# tinyG2Hat.net
KiCad netlist of a schematic drawn in EAGLE
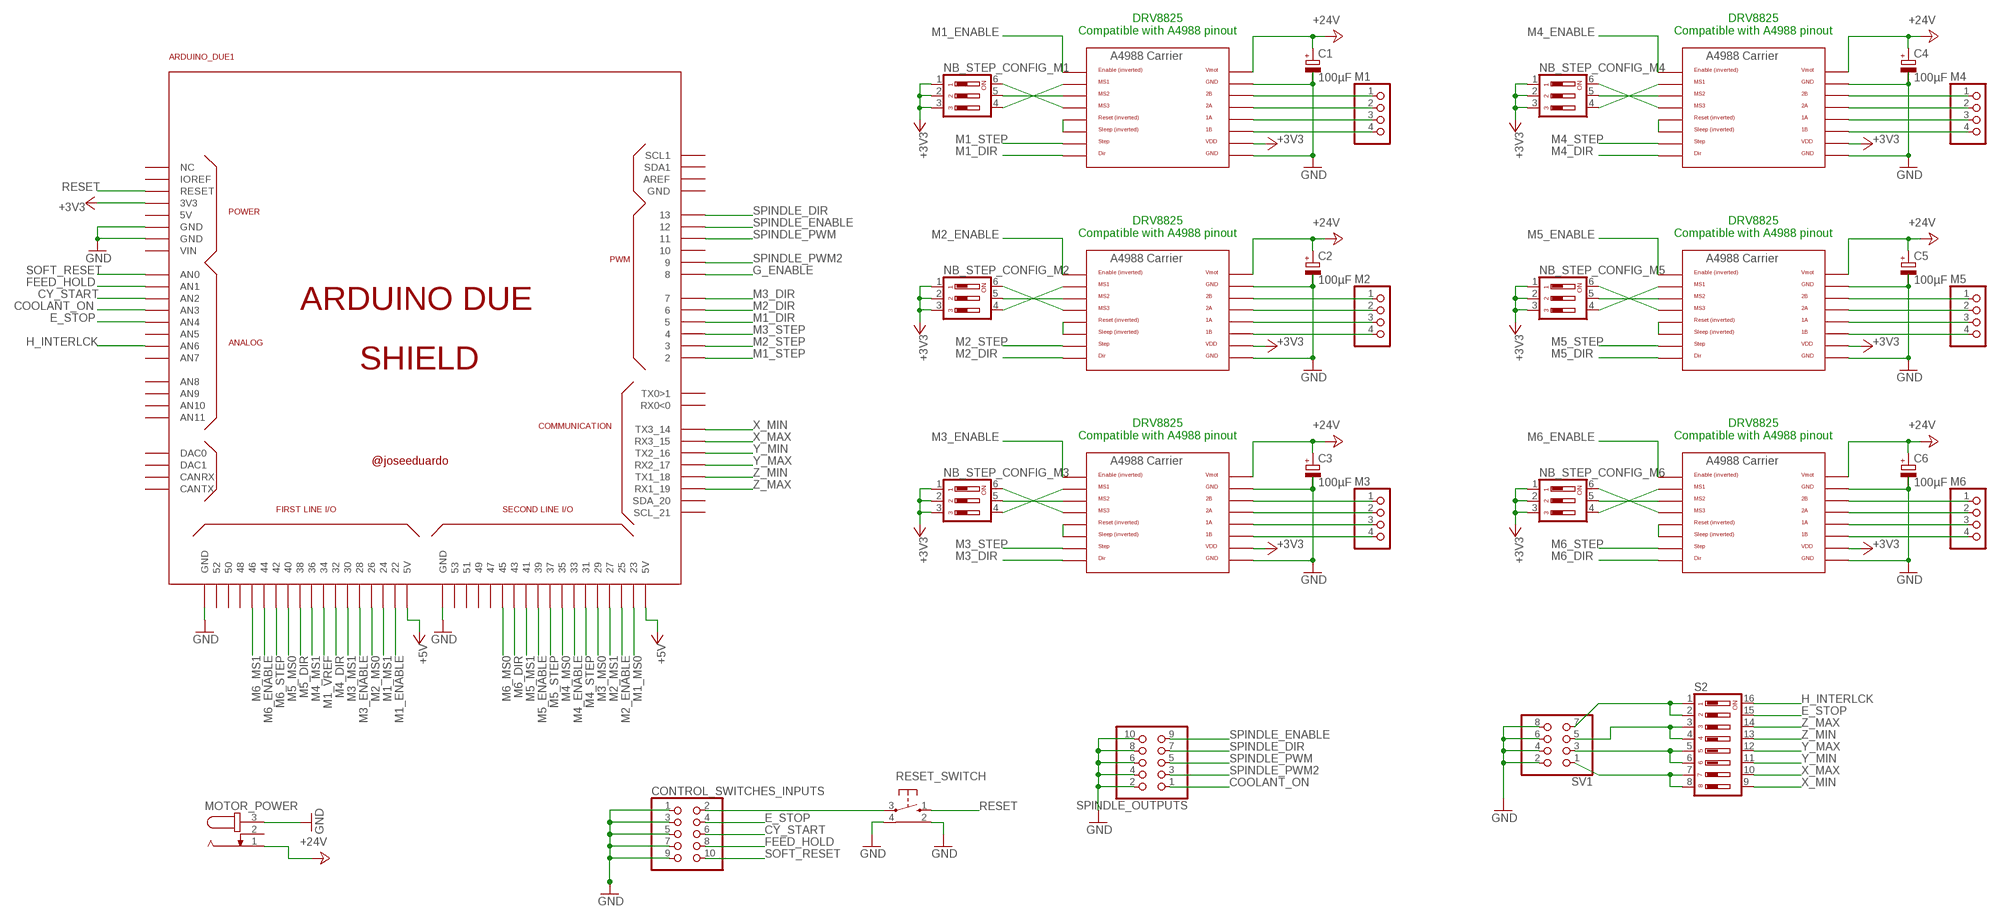
[diagram p0: schematic, sheet 1]

(export (version "E")
  (design (tool "Eeschema 10.0.6"))
  (components
    (comp (ref "ARDUINO_DUE1")
      (value "ARDUINO_DUE_SHIELD_NOSPI")
      (footprint "eagle-import:ARDUINO_DUE_SHIELD_NOSPI")
      (libsource (lib "eagle-import") (part "ARDUINO_DUE_SHIELD_NOSPI"))
    )
    (comp (ref "C1")
      (value "100µF")
      (footprint "eagle-import:E3,5-8")
      (libsource (lib "eagle-import") (part "CPOL-EUE3.5-8"))
    )
    (comp (ref "C2")
      (value "100µF")
      (footprint "eagle-import:E3,5-8")
      (libsource (lib "eagle-import") (part "CPOL-EUE3.5-8"))
    )
    (comp (ref "C3")
      (value "100µF")
      (footprint "eagle-import:E3,5-8")
      (libsource (lib "eagle-import") (part "CPOL-EUE3.5-8"))
    )
    (comp (ref "C4")
      (value "100µF")
      (footprint "eagle-import:E3,5-8")
      (libsource (lib "eagle-import") (part "CPOL-EUE3.5-8"))
    )
    (comp (ref "C5")
      (value "100µF")
      (footprint "eagle-import:E3,5-8")
      (libsource (lib "eagle-import") (part "CPOL-EUE3.5-8"))
    )
    (comp (ref "C6")
      (value "100µF")
      (footprint "eagle-import:E3,5-8")
      (libsource (lib "eagle-import") (part "CPOL-EUE3.5-8"))
    )
    (comp (ref "CONTROL_SWITCHES_INPUTS")
      (value "PINHD-2X5")
      (footprint "eagle-import:2X05")
      (libsource (lib "eagle-import") (part "PINHD-2X5"))
    )
    (comp (ref "M1")
      (value "PINHD-1X4")
      (footprint "eagle-import:1X04")
      (libsource (lib "eagle-import") (part "PINHD-1X4"))
    )
    (comp (ref "M2")
      (value "PINHD-1X4")
      (footprint "eagle-import:1X04")
      (libsource (lib "eagle-import") (part "PINHD-1X4"))
    )
    (comp (ref "M3")
      (value "PINHD-1X4")
      (footprint "eagle-import:1X04")
      (libsource (lib "eagle-import") (part "PINHD-1X4"))
    )
    (comp (ref "M4")
      (value "PINHD-1X4")
      (footprint "eagle-import:1X04")
      (libsource (lib "eagle-import") (part "PINHD-1X4"))
    )
    (comp (ref "M5")
      (value "PINHD-1X4")
      (footprint "eagle-import:1X04")
      (libsource (lib "eagle-import") (part "PINHD-1X4"))
    )
    (comp (ref "M6")
      (value "PINHD-1X4")
      (footprint "eagle-import:1X04")
      (libsource (lib "eagle-import") (part "PINHD-1X4"))
    )
    (comp (ref "MOTOR_POWER")
      (value "RAPC7120")
      (footprint "eagle-import:RAPC712")
      (libsource (lib "eagle-import") (part "RAPC7120"))
    )
    (comp (ref "NB_STEP_CONFIG_M1")
      (value "DIP03YL")
      (footprint "eagle-import:DIP03YL")
      (libsource (lib "eagle-import") (part "DIP03YL"))
    )
    (comp (ref "NB_STEP_CONFIG_M2")
      (value "DIP03YL")
      (footprint "eagle-import:DIP03YL")
      (libsource (lib "eagle-import") (part "DIP03YL"))
    )
    (comp (ref "NB_STEP_CONFIG_M3")
      (value "DIP03YL")
      (footprint "eagle-import:DIP03YL")
      (libsource (lib "eagle-import") (part "DIP03YL"))
    )
    (comp (ref "NB_STEP_CONFIG_M4")
      (value "DIP03YL")
      (footprint "eagle-import:DIP03YL")
      (libsource (lib "eagle-import") (part "DIP03YL"))
    )
    (comp (ref "NB_STEP_CONFIG_M5")
      (value "DIP03YL")
      (footprint "eagle-import:DIP03YL")
      (libsource (lib "eagle-import") (part "DIP03YL"))
    )
    (comp (ref "NB_STEP_CONFIG_M6")
      (value "DIP03YL")
      (footprint "eagle-import:DIP03YL")
      (libsource (lib "eagle-import") (part "DIP03YL"))
    )
    (comp (ref "RESET_SWITCH")
      (value "10-XX-RPAD")
      (footprint "eagle-import:B3F-10XX-RPAD")
      (libsource (lib "eagle-import") (part "10-XX-RPAD"))
    )
    (comp (ref "S2")
      (value "DIP08YL")
      (footprint "eagle-import:DIP08YL")
      (libsource (lib "eagle-import") (part "DIP08YL"))
    )
    (comp (ref "SPINDLE_OUTPUTS")
      (value "PINHD-2X5")
      (footprint "eagle-import:2X05")
      (libsource (lib "eagle-import") (part "PINHD-2X5"))
    )
    (comp (ref "SV1")
      (value "PINHD-2X4")
      (footprint "eagle-import:2X04")
      (libsource (lib "eagle-import") (part "PINHD-2X4"))
    )
    (comp (ref "U$1")
      (value "A4988BREAKOUT")
      (footprint "eagle-import:A4988BREAKOUT")
      (libsource (lib "eagle-import") (part "A4988BREAKOUT"))
    )
    (comp (ref "U$2")
      (value "A4988BREAKOUT")
      (footprint "eagle-import:A4988BREAKOUT")
      (libsource (lib "eagle-import") (part "A4988BREAKOUT"))
    )
    (comp (ref "U$3")
      (value "A4988BREAKOUT")
      (footprint "eagle-import:A4988BREAKOUT")
      (libsource (lib "eagle-import") (part "A4988BREAKOUT"))
    )
    (comp (ref "U$4")
      (value "A4988BREAKOUT")
      (footprint "eagle-import:A4988BREAKOUT")
      (libsource (lib "eagle-import") (part "A4988BREAKOUT"))
    )
    (comp (ref "U$5")
      (value "A4988BREAKOUT")
      (footprint "eagle-import:A4988BREAKOUT")
      (libsource (lib "eagle-import") (part "A4988BREAKOUT"))
    )
    (comp (ref "U$6")
      (value "A4988BREAKOUT")
      (footprint "eagle-import:A4988BREAKOUT")
      (libsource (lib "eagle-import") (part "A4988BREAKOUT"))
    )
  )
  (nets
    (net (code "1") (name "+3V3") (class "Default")
      (node (ref "ARDUINO_DUE1") (pin "3V3") (pinfunction "3V3_3V3") (pintype "bidirectional"))
      (node (ref "NB_STEP_CONFIG_M1") (pin "1") (pinfunction "1_1") (pintype "passive"))
      (node (ref "NB_STEP_CONFIG_M1") (pin "2") (pinfunction "2_2") (pintype "passive"))
      (node (ref "NB_STEP_CONFIG_M1") (pin "3") (pinfunction "3_3") (pintype "passive"))
      (node (ref "NB_STEP_CONFIG_M2") (pin "1") (pinfunction "1_1") (pintype "passive"))
      (node (ref "NB_STEP_CONFIG_M2") (pin "2") (pinfunction "2_2") (pintype "passive"))
      (node (ref "NB_STEP_CONFIG_M2") (pin "3") (pinfunction "3_3") (pintype "passive"))
      (node (ref "NB_STEP_CONFIG_M3") (pin "1") (pinfunction "1_1") (pintype "passive"))
      (node (ref "NB_STEP_CONFIG_M3") (pin "2") (pinfunction "2_2") (pintype "passive"))
      (node (ref "NB_STEP_CONFIG_M3") (pin "3") (pinfunction "3_3") (pintype "passive"))
      (node (ref "NB_STEP_CONFIG_M4") (pin "1") (pinfunction "1_1") (pintype "passive"))
      (node (ref "NB_STEP_CONFIG_M4") (pin "2") (pinfunction "2_2") (pintype "passive"))
      (node (ref "NB_STEP_CONFIG_M4") (pin "3") (pinfunction "3_3") (pintype "passive"))
      (node (ref "NB_STEP_CONFIG_M5") (pin "1") (pinfunction "1_1") (pintype "passive"))
      (node (ref "NB_STEP_CONFIG_M5") (pin "2") (pinfunction "2_2") (pintype "passive"))
      (node (ref "NB_STEP_CONFIG_M5") (pin "3") (pinfunction "3_3") (pintype "passive"))
      (node (ref "NB_STEP_CONFIG_M6") (pin "1") (pinfunction "1_1") (pintype "passive"))
      (node (ref "NB_STEP_CONFIG_M6") (pin "2") (pinfunction "2_2") (pintype "passive"))
      (node (ref "NB_STEP_CONFIG_M6") (pin "3") (pinfunction "3_3") (pintype "passive"))
      (node (ref "U$1") (pin "VDD") (pinfunction "VDD_VDD") (pintype "power_in"))
      (node (ref "U$2") (pin "VDD") (pinfunction "VDD_VDD") (pintype "power_in"))
      (node (ref "U$3") (pin "VDD") (pinfunction "VDD_VDD") (pintype "power_in"))
      (node (ref "U$4") (pin "VDD") (pinfunction "VDD_VDD") (pintype "power_in"))
      (node (ref "U$5") (pin "VDD") (pinfunction "VDD_VDD") (pintype "power_in"))
      (node (ref "U$6") (pin "VDD") (pinfunction "VDD_VDD") (pintype "power_in"))
    )
    (net (code "2") (name "+5V") (class "Default")
      (node (ref "ARDUINO_DUE1") (pin "5V0_1") (pinfunction "5V_5V0_1") (pintype "bidirectional"))
      (node (ref "ARDUINO_DUE1") (pin "5V0_2") (pinfunction "5V_5V0_2") (pintype "bidirectional"))
    )
    (net (code "3") (name "+24V") (class "Default")
      (node (ref "C1") (pin "+") (pinfunction "+_+") (pintype "passive"))
      (node (ref "C2") (pin "+") (pinfunction "+_+") (pintype "passive"))
      (node (ref "C3") (pin "+") (pinfunction "+_+") (pintype "passive"))
      (node (ref "C4") (pin "+") (pinfunction "+_+") (pintype "passive"))
      (node (ref "C5") (pin "+") (pinfunction "+_+") (pintype "passive"))
      (node (ref "C6") (pin "+") (pinfunction "+_+") (pintype "passive"))
      (node (ref "MOTOR_POWER") (pin "1") (pinfunction "1_1") (pintype "passive"))
      (node (ref "U$1") (pin "VMOT") (pinfunction "VMOT_VMOT") (pintype "power_in"))
      (node (ref "U$2") (pin "VMOT") (pinfunction "VMOT_VMOT") (pintype "power_in"))
      (node (ref "U$3") (pin "VMOT") (pinfunction "VMOT_VMOT") (pintype "power_in"))
      (node (ref "U$4") (pin "VMOT") (pinfunction "VMOT_VMOT") (pintype "power_in"))
      (node (ref "U$5") (pin "VMOT") (pinfunction "VMOT_VMOT") (pintype "power_in"))
      (node (ref "U$6") (pin "VMOT") (pinfunction "VMOT_VMOT") (pintype "power_in"))
    )
    (net (code "4") (name "/COOLANT_ON") (class "Default")
      (node (ref "ARDUINO_DUE1") (pin "A3") (pinfunction "AN3_A3") (pintype "bidirectional"))
      (node (ref "SPINDLE_OUTPUTS") (pin "1") (pinfunction "1_1") (pintype "passive"))
    )
    (net (code "5") (name "/CY_START") (class "Default")
      (node (ref "ARDUINO_DUE1") (pin "A2") (pinfunction "AN2_A2") (pintype "bidirectional"))
      (node (ref "CONTROL_SWITCHES_INPUTS") (pin "6") (pinfunction "6_6") (pintype "passive"))
    )
    (net (code "6") (name "/E_STOP") (class "Default")
      (node (ref "ARDUINO_DUE1") (pin "A4") (pinfunction "AN4_A4") (pintype "bidirectional"))
      (node (ref "CONTROL_SWITCHES_INPUTS") (pin "4") (pinfunction "4_4") (pintype "passive"))
      (node (ref "S2") (pin "15") (pinfunction "15_15") (pintype "passive"))
    )
    (net (code "7") (name "/FEED_HOLD") (class "Default")
      (node (ref "ARDUINO_DUE1") (pin "A1") (pinfunction "AN1_A1") (pintype "bidirectional"))
      (node (ref "CONTROL_SWITCHES_INPUTS") (pin "8") (pinfunction "8_8") (pintype "passive"))
    )
    (net (code "8") (name "/G_ENABLE") (class "Default")
      (node (ref "ARDUINO_DUE1") (pin "8") (pinfunction "8_8") (pintype "bidirectional"))
    )
    (net (code "9") (name "/H_INTERLCK") (class "Default")
      (node (ref "ARDUINO_DUE1") (pin "A6") (pinfunction "AN6_A6") (pintype "bidirectional"))
      (node (ref "S2") (pin "16") (pinfunction "16_16") (pintype "passive"))
    )
    (net (code "10") (name "/M1_DIR") (class "Default")
      (node (ref "ARDUINO_DUE1") (pin "5") (pinfunction "5_5") (pintype "bidirectional"))
      (node (ref "U$1") (pin "DIR") (pinfunction "DIR_DIR") (pintype "input"))
    )
    (net (code "11") (name "/M1_ENABLE") (class "Default")
      (node (ref "ARDUINO_DUE1") (pin "22") (pinfunction "22_22") (pintype "bidirectional"))
      (node (ref "U$1") (pin "EN") (pinfunction "EN_EN") (pintype "input"))
    )
    (net (code "12") (name "/M1_MS0") (class "Default")
      (node (ref "ARDUINO_DUE1") (pin "23") (pinfunction "23_23") (pintype "bidirectional"))
    )
    (net (code "13") (name "/M1_MS1") (class "Default")
      (node (ref "ARDUINO_DUE1") (pin "24") (pinfunction "24_24") (pintype "bidirectional"))
    )
    (net (code "14") (name "/M1_STEP") (class "Default")
      (node (ref "ARDUINO_DUE1") (pin "2") (pinfunction "2_2") (pintype "bidirectional"))
      (node (ref "U$1") (pin "STEP") (pinfunction "STEP_STEP") (pintype "input"))
    )
    (net (code "15") (name "/M1_VREF") (class "Default")
      (node (ref "ARDUINO_DUE1") (pin "34") (pinfunction "34_34") (pintype "bidirectional"))
    )
    (net (code "16") (name "/M2_DIR") (class "Default")
      (node (ref "ARDUINO_DUE1") (pin "6") (pinfunction "6_6") (pintype "bidirectional"))
      (node (ref "U$2") (pin "DIR") (pinfunction "DIR_DIR") (pintype "input"))
    )
    (net (code "17") (name "/M2_ENABLE") (class "Default")
      (node (ref "ARDUINO_DUE1") (pin "25") (pinfunction "25_25") (pintype "bidirectional"))
      (node (ref "U$2") (pin "EN") (pinfunction "EN_EN") (pintype "input"))
    )
    (net (code "18") (name "/M2_MS0") (class "Default")
      (node (ref "ARDUINO_DUE1") (pin "26") (pinfunction "26_26") (pintype "bidirectional"))
    )
    (net (code "19") (name "/M2_MS1") (class "Default")
      (node (ref "ARDUINO_DUE1") (pin "27") (pinfunction "27_27") (pintype "bidirectional"))
    )
    (net (code "20") (name "/M2_STEP") (class "Default")
      (node (ref "ARDUINO_DUE1") (pin "3") (pinfunction "3_3") (pintype "bidirectional"))
      (node (ref "U$2") (pin "STEP") (pinfunction "STEP_STEP") (pintype "input"))
    )
    (net (code "21") (name "/M3_DIR") (class "Default")
      (node (ref "ARDUINO_DUE1") (pin "7") (pinfunction "7_7") (pintype "bidirectional"))
      (node (ref "U$3") (pin "DIR") (pinfunction "DIR_DIR") (pintype "input"))
    )
    (net (code "22") (name "/M3_ENABLE") (class "Default")
      (node (ref "ARDUINO_DUE1") (pin "28") (pinfunction "28_28") (pintype "bidirectional"))
      (node (ref "U$3") (pin "EN") (pinfunction "EN_EN") (pintype "input"))
    )
    (net (code "23") (name "/M3_MS0") (class "Default")
      (node (ref "ARDUINO_DUE1") (pin "29") (pinfunction "29_29") (pintype "bidirectional"))
    )
    (net (code "24") (name "/M3_MS1") (class "Default")
      (node (ref "ARDUINO_DUE1") (pin "30") (pinfunction "30_30") (pintype "bidirectional"))
    )
    (net (code "25") (name "/M3_STEP") (class "Default")
      (node (ref "ARDUINO_DUE1") (pin "4") (pinfunction "4_4") (pintype "bidirectional"))
      (node (ref "U$3") (pin "STEP") (pinfunction "STEP_STEP") (pintype "input"))
    )
    (net (code "26") (name "/M4_DIR") (class "Default")
      (node (ref "ARDUINO_DUE1") (pin "32") (pinfunction "32_32") (pintype "bidirectional"))
      (node (ref "U$4") (pin "DIR") (pinfunction "DIR_DIR") (pintype "input"))
    )
    (net (code "27") (name "/M4_ENABLE") (class "Default")
      (node (ref "ARDUINO_DUE1") (pin "33") (pinfunction "33_33") (pintype "bidirectional"))
      (node (ref "U$4") (pin "EN") (pinfunction "EN_EN") (pintype "input"))
    )
    (net (code "28") (name "/M4_MS0") (class "Default")
      (node (ref "ARDUINO_DUE1") (pin "35") (pinfunction "35_35") (pintype "bidirectional"))
    )
    (net (code "29") (name "/M4_MS1") (class "Default")
      (node (ref "ARDUINO_DUE1") (pin "36") (pinfunction "36_36") (pintype "bidirectional"))
    )
    (net (code "30") (name "/M4_STEP") (class "Default")
      (node (ref "ARDUINO_DUE1") (pin "31") (pinfunction "31_31") (pintype "bidirectional"))
      (node (ref "U$4") (pin "STEP") (pinfunction "STEP_STEP") (pintype "input"))
    )
    (net (code "31") (name "/M5_DIR") (class "Default")
      (node (ref "ARDUINO_DUE1") (pin "38") (pinfunction "38_38") (pintype "bidirectional"))
      (node (ref "U$5") (pin "DIR") (pinfunction "DIR_DIR") (pintype "input"))
    )
    (net (code "32") (name "/M5_ENABLE") (class "Default")
      (node (ref "ARDUINO_DUE1") (pin "39") (pinfunction "39_39") (pintype "bidirectional"))
      (node (ref "U$5") (pin "EN") (pinfunction "EN_EN") (pintype "input"))
    )
    (net (code "33") (name "/M5_MS0") (class "Default")
      (node (ref "ARDUINO_DUE1") (pin "40") (pinfunction "40_40") (pintype "bidirectional"))
    )
    (net (code "34") (name "/M5_MS1") (class "Default")
      (node (ref "ARDUINO_DUE1") (pin "41") (pinfunction "41_41") (pintype "bidirectional"))
    )
    (net (code "35") (name "/M5_STEP") (class "Default")
      (node (ref "ARDUINO_DUE1") (pin "37") (pinfunction "37_37") (pintype "bidirectional"))
      (node (ref "U$5") (pin "STEP") (pinfunction "STEP_STEP") (pintype "input"))
    )
    (net (code "36") (name "/M6_DIR") (class "Default")
      (node (ref "ARDUINO_DUE1") (pin "43") (pinfunction "43_43") (pintype "bidirectional"))
      (node (ref "U$6") (pin "DIR") (pinfunction "DIR_DIR") (pintype "input"))
    )
    (net (code "37") (name "/M6_ENABLE") (class "Default")
      (node (ref "ARDUINO_DUE1") (pin "44") (pinfunction "44_44") (pintype "bidirectional"))
      (node (ref "U$6") (pin "EN") (pinfunction "EN_EN") (pintype "input"))
    )
    (net (code "38") (name "/M6_MS0") (class "Default")
      (node (ref "ARDUINO_DUE1") (pin "45") (pinfunction "45_45") (pintype "bidirectional"))
    )
    (net (code "39") (name "/M6_MS1") (class "Default")
      (node (ref "ARDUINO_DUE1") (pin "46") (pinfunction "46_46") (pintype "bidirectional"))
    )
    (net (code "40") (name "/M6_STEP") (class "Default")
      (node (ref "ARDUINO_DUE1") (pin "42") (pinfunction "42_42") (pintype "bidirectional"))
      (node (ref "U$6") (pin "STEP") (pinfunction "STEP_STEP") (pintype "input"))
    )
    (net (code "41") (name "/RESET") (class "Default")
      (node (ref "ARDUINO_DUE1") (pin "RESET") (pinfunction "RESET_RESET") (pintype "bidirectional"))
      (node (ref "RESET_SWITCH") (pin "1") (pinfunction "S_1") (pintype "passive"))
    )
    (net (code "42") (name "/SOFT_RESET") (class "Default")
      (node (ref "ARDUINO_DUE1") (pin "A0") (pinfunction "AN0_A0") (pintype "bidirectional"))
      (node (ref "CONTROL_SWITCHES_INPUTS") (pin "10") (pinfunction "10_10") (pintype "passive"))
    )
    (net (code "43") (name "/SPINDLE_DIR") (class "Default")
      (node (ref "ARDUINO_DUE1") (pin "13") (pinfunction "13_13") (pintype "bidirectional"))
      (node (ref "SPINDLE_OUTPUTS") (pin "7") (pinfunction "7_7") (pintype "passive"))
    )
    (net (code "44") (name "/SPINDLE_ENABLE") (class "Default")
      (node (ref "ARDUINO_DUE1") (pin "12") (pinfunction "12_12") (pintype "bidirectional"))
      (node (ref "SPINDLE_OUTPUTS") (pin "9") (pinfunction "9_9") (pintype "passive"))
    )
    (net (code "45") (name "/SPINDLE_PWM") (class "Default")
      (node (ref "ARDUINO_DUE1") (pin "11") (pinfunction "11_11") (pintype "bidirectional"))
      (node (ref "SPINDLE_OUTPUTS") (pin "5") (pinfunction "5_5") (pintype "passive"))
    )
    (net (code "46") (name "/SPINDLE_PWM2") (class "Default")
      (node (ref "ARDUINO_DUE1") (pin "9") (pinfunction "9_9") (pintype "bidirectional"))
      (node (ref "SPINDLE_OUTPUTS") (pin "3") (pinfunction "3_3") (pintype "passive"))
    )
    (net (code "47") (name "/X_MAX") (class "Default")
      (node (ref "ARDUINO_DUE1") (pin "15") (pinfunction "RX3_15_15") (pintype "bidirectional"))
      (node (ref "S2") (pin "10") (pinfunction "10_10") (pintype "passive"))
    )
    (net (code "48") (name "/X_MIN") (class "Default")
      (node (ref "ARDUINO_DUE1") (pin "14") (pinfunction "TX3_14_14") (pintype "bidirectional"))
      (node (ref "S2") (pin "9") (pinfunction "9_9") (pintype "passive"))
    )
    (net (code "49") (name "/Y_MAX") (class "Default")
      (node (ref "ARDUINO_DUE1") (pin "17") (pinfunction "RX2_17_17") (pintype "bidirectional"))
      (node (ref "S2") (pin "12") (pinfunction "12_12") (pintype "passive"))
    )
    (net (code "50") (name "/Y_MIN") (class "Default")
      (node (ref "ARDUINO_DUE1") (pin "16") (pinfunction "TX2_16_16") (pintype "bidirectional"))
      (node (ref "S2") (pin "11") (pinfunction "11_11") (pintype "passive"))
    )
    (net (code "51") (name "/Z_MAX") (class "Default")
      (node (ref "ARDUINO_DUE1") (pin "19") (pinfunction "RX1_19_19") (pintype "bidirectional"))
      (node (ref "S2") (pin "14") (pinfunction "14_14") (pintype "passive"))
    )
    (net (code "52") (name "/Z_MIN") (class "Default")
      (node (ref "ARDUINO_DUE1") (pin "18") (pinfunction "TX1_18_18") (pintype "bidirectional"))
      (node (ref "S2") (pin "13") (pinfunction "13_13") (pintype "passive"))
    )
    (net (code "53") (name "GND") (class "Default")
      (node (ref "ARDUINO_DUE1") (pin "GND") (pinfunction "GND_GND") (pintype "bidirectional"))
      (node (ref "ARDUINO_DUE1") (pin "GND_1") (pinfunction "GND_GND_1") (pintype "bidirectional"))
      (node (ref "ARDUINO_DUE1") (pin "GND_2") (pinfunction "GND_GND_2") (pintype "bidirectional"))
      (node (ref "ARDUINO_DUE1") (pin "GND_3") (pinfunction "GND_GND_3") (pintype "bidirectional"))
      (node (ref "C1") (pin "-") (pinfunction "-_-") (pintype "passive"))
      (node (ref "C2") (pin "-") (pinfunction "-_-") (pintype "passive"))
      (node (ref "C3") (pin "-") (pinfunction "-_-") (pintype "passive"))
      (node (ref "C4") (pin "-") (pinfunction "-_-") (pintype "passive"))
      (node (ref "C5") (pin "-") (pinfunction "-_-") (pintype "passive"))
      (node (ref "C6") (pin "-") (pinfunction "-_-") (pintype "passive"))
      (node (ref "CONTROL_SWITCHES_INPUTS") (pin "1") (pinfunction "1_1") (pintype "passive"))
      (node (ref "CONTROL_SWITCHES_INPUTS") (pin "3") (pinfunction "3_3") (pintype "passive"))
      (node (ref "CONTROL_SWITCHES_INPUTS") (pin "5") (pinfunction "5_5") (pintype "passive"))
      (node (ref "CONTROL_SWITCHES_INPUTS") (pin "7") (pinfunction "7_7") (pintype "passive"))
      (node (ref "CONTROL_SWITCHES_INPUTS") (pin "9") (pinfunction "9_9") (pintype "passive"))
      (node (ref "MOTOR_POWER") (pin "3") (pinfunction "3_3") (pintype "passive"))
      (node (ref "RESET_SWITCH") (pin "2") (pinfunction "GND1_2") (pintype "passive"))
      (node (ref "RESET_SWITCH") (pin "4") (pinfunction "GND2_4") (pintype "passive"))
      (node (ref "SPINDLE_OUTPUTS") (pin "10") (pinfunction "10_10") (pintype "passive"))
      (node (ref "SPINDLE_OUTPUTS") (pin "2") (pinfunction "2_2") (pintype "passive"))
      (node (ref "SPINDLE_OUTPUTS") (pin "4") (pinfunction "4_4") (pintype "passive"))
      (node (ref "SPINDLE_OUTPUTS") (pin "6") (pinfunction "6_6") (pintype "passive"))
      (node (ref "SPINDLE_OUTPUTS") (pin "8") (pinfunction "8_8") (pintype "passive"))
      (node (ref "SV1") (pin "2") (pinfunction "2_2") (pintype "passive"))
      (node (ref "SV1") (pin "4") (pinfunction "4_4") (pintype "passive"))
      (node (ref "SV1") (pin "6") (pinfunction "6_6") (pintype "passive"))
      (node (ref "SV1") (pin "8") (pinfunction "8_8") (pintype "passive"))
      (node (ref "U$1") (pin "GND") (pinfunction "GND_GND") (pintype "power_in"))
      (node (ref "U$1") (pin "GND@0") (pinfunction "GND_GND@0") (pintype "power_in"))
      (node (ref "U$2") (pin "GND") (pinfunction "GND_GND") (pintype "power_in"))
      (node (ref "U$2") (pin "GND@0") (pinfunction "GND_GND@0") (pintype "power_in"))
      (node (ref "U$3") (pin "GND") (pinfunction "GND_GND") (pintype "power_in"))
      (node (ref "U$3") (pin "GND@0") (pinfunction "GND_GND@0") (pintype "power_in"))
      (node (ref "U$4") (pin "GND") (pinfunction "GND_GND") (pintype "power_in"))
      (node (ref "U$4") (pin "GND@0") (pinfunction "GND_GND@0") (pintype "power_in"))
      (node (ref "U$5") (pin "GND") (pinfunction "GND_GND") (pintype "power_in"))
      (node (ref "U$5") (pin "GND@0") (pinfunction "GND_GND@0") (pintype "power_in"))
      (node (ref "U$6") (pin "GND") (pinfunction "GND_GND") (pintype "power_in"))
      (node (ref "U$6") (pin "GND@0") (pinfunction "GND_GND@0") (pintype "power_in"))
    )
    (net (code "54") (name "Net-(M1-Pad1)") (class "Default")
      (node (ref "M1") (pin "1") (pinfunction "1_1") (pintype "passive"))
      (node (ref "U$1") (pin "2B") (pinfunction "2B_2B") (pintype "output"))
    )
    (net (code "55") (name "Net-(M1-Pad2)") (class "Default")
      (node (ref "M1") (pin "2") (pinfunction "2_2") (pintype "passive"))
      (node (ref "U$1") (pin "2A") (pinfunction "2A_2A") (pintype "output"))
    )
    (net (code "56") (name "Net-(M1-Pad3)") (class "Default")
      (node (ref "M1") (pin "3") (pinfunction "3_3") (pintype "passive"))
      (node (ref "U$1") (pin "1A") (pinfunction "1A_1A") (pintype "output"))
    )
    (net (code "57") (name "Net-(M1-Pad4)") (class "Default")
      (node (ref "M1") (pin "4") (pinfunction "4_4") (pintype "passive"))
      (node (ref "U$1") (pin "1B") (pinfunction "1B_1B") (pintype "output"))
    )
    (net (code "58") (name "Net-(M2-Pad1)") (class "Default")
      (node (ref "M2") (pin "1") (pinfunction "1_1") (pintype "passive"))
      (node (ref "U$2") (pin "2B") (pinfunction "2B_2B") (pintype "output"))
    )
    (net (code "59") (name "Net-(M2-Pad2)") (class "Default")
      (node (ref "M2") (pin "2") (pinfunction "2_2") (pintype "passive"))
      (node (ref "U$2") (pin "2A") (pinfunction "2A_2A") (pintype "output"))
    )
    (net (code "60") (name "Net-(M2-Pad3)") (class "Default")
      (node (ref "M2") (pin "3") (pinfunction "3_3") (pintype "passive"))
      (node (ref "U$2") (pin "1A") (pinfunction "1A_1A") (pintype "output"))
    )
    (net (code "61") (name "Net-(M2-Pad4)") (class "Default")
      (node (ref "M2") (pin "4") (pinfunction "4_4") (pintype "passive"))
      (node (ref "U$2") (pin "1B") (pinfunction "1B_1B") (pintype "output"))
    )
    (net (code "62") (name "Net-(M3-Pad1)") (class "Default")
      (node (ref "M3") (pin "1") (pinfunction "1_1") (pintype "passive"))
      (node (ref "U$3") (pin "2B") (pinfunction "2B_2B") (pintype "output"))
    )
    (net (code "63") (name "Net-(M3-Pad2)") (class "Default")
      (node (ref "M3") (pin "2") (pinfunction "2_2") (pintype "passive"))
      (node (ref "U$3") (pin "2A") (pinfunction "2A_2A") (pintype "output"))
    )
    (net (code "64") (name "Net-(M3-Pad3)") (class "Default")
      (node (ref "M3") (pin "3") (pinfunction "3_3") (pintype "passive"))
      (node (ref "U$3") (pin "1A") (pinfunction "1A_1A") (pintype "output"))
    )
    (net (code "65") (name "Net-(M3-Pad4)") (class "Default")
      (node (ref "M3") (pin "4") (pinfunction "4_4") (pintype "passive"))
      (node (ref "U$3") (pin "1B") (pinfunction "1B_1B") (pintype "output"))
    )
    (net (code "66") (name "Net-(M4-Pad1)") (class "Default")
      (node (ref "M4") (pin "1") (pinfunction "1_1") (pintype "passive"))
      (node (ref "U$4") (pin "2B") (pinfunction "2B_2B") (pintype "output"))
    )
    (net (code "67") (name "Net-(M4-Pad2)") (class "Default")
      (node (ref "M4") (pin "2") (pinfunction "2_2") (pintype "passive"))
      (node (ref "U$4") (pin "2A") (pinfunction "2A_2A") (pintype "output"))
    )
    (net (code "68") (name "Net-(M4-Pad3)") (class "Default")
      (node (ref "M4") (pin "3") (pinfunction "3_3") (pintype "passive"))
      (node (ref "U$4") (pin "1A") (pinfunction "1A_1A") (pintype "output"))
    )
    (net (code "69") (name "Net-(M4-Pad4)") (class "Default")
      (node (ref "M4") (pin "4") (pinfunction "4_4") (pintype "passive"))
      (node (ref "U$4") (pin "1B") (pinfunction "1B_1B") (pintype "output"))
    )
    (net (code "70") (name "Net-(M5-Pad1)") (class "Default")
      (node (ref "M5") (pin "1") (pinfunction "1_1") (pintype "passive"))
      (node (ref "U$5") (pin "2B") (pinfunction "2B_2B") (pintype "output"))
    )
    (net (code "71") (name "Net-(M5-Pad2)") (class "Default")
      (node (ref "M5") (pin "2") (pinfunction "2_2") (pintype "passive"))
      (node (ref "U$5") (pin "2A") (pinfunction "2A_2A") (pintype "output"))
    )
    (net (code "72") (name "Net-(M5-Pad3)") (class "Default")
      (node (ref "M5") (pin "3") (pinfunction "3_3") (pintype "passive"))
      (node (ref "U$5") (pin "1A") (pinfunction "1A_1A") (pintype "output"))
    )
    (net (code "73") (name "Net-(M5-Pad4)") (class "Default")
      (node (ref "M5") (pin "4") (pinfunction "4_4") (pintype "passive"))
      (node (ref "U$5") (pin "1B") (pinfunction "1B_1B") (pintype "output"))
    )
    (net (code "74") (name "Net-(M6-Pad1)") (class "Default")
      (node (ref "M6") (pin "1") (pinfunction "1_1") (pintype "passive"))
      (node (ref "U$6") (pin "2B") (pinfunction "2B_2B") (pintype "output"))
    )
    (net (code "75") (name "Net-(M6-Pad2)") (class "Default")
      (node (ref "M6") (pin "2") (pinfunction "2_2") (pintype "passive"))
      (node (ref "U$6") (pin "2A") (pinfunction "2A_2A") (pintype "output"))
    )
    (net (code "76") (name "Net-(M6-Pad3)") (class "Default")
      (node (ref "M6") (pin "3") (pinfunction "3_3") (pintype "passive"))
      (node (ref "U$6") (pin "1A") (pinfunction "1A_1A") (pintype "output"))
    )
    (net (code "77") (name "Net-(M6-Pad4)") (class "Default")
      (node (ref "M6") (pin "4") (pinfunction "4_4") (pintype "passive"))
      (node (ref "U$6") (pin "1B") (pinfunction "1B_1B") (pintype "output"))
    )
    (net (code "78") (name "Net-(NB_STEP_CONFIG_M1-Pad4)") (class "Default")
      (node (ref "NB_STEP_CONFIG_M1") (pin "4") (pinfunction "4_4") (pintype "passive"))
      (node (ref "U$1") (pin "MS1") (pinfunction "MS1_MS1") (pintype "input"))
    )
    (net (code "79") (name "Net-(NB_STEP_CONFIG_M1-Pad5)") (class "Default")
      (node (ref "NB_STEP_CONFIG_M1") (pin "5") (pinfunction "5_5") (pintype "passive"))
      (node (ref "U$1") (pin "MS2") (pinfunction "MS2_MS2") (pintype "input"))
    )
    (net (code "80") (name "Net-(NB_STEP_CONFIG_M1-Pad6)") (class "Default")
      (node (ref "NB_STEP_CONFIG_M1") (pin "6") (pinfunction "6_6") (pintype "passive"))
      (node (ref "U$1") (pin "MS3") (pinfunction "MS3_MS3") (pintype "input"))
    )
    (net (code "81") (name "Net-(NB_STEP_CONFIG_M2-Pad4)") (class "Default")
      (node (ref "NB_STEP_CONFIG_M2") (pin "4") (pinfunction "4_4") (pintype "passive"))
      (node (ref "U$2") (pin "MS1") (pinfunction "MS1_MS1") (pintype "input"))
    )
    (net (code "82") (name "Net-(NB_STEP_CONFIG_M2-Pad5)") (class "Default")
      (node (ref "NB_STEP_CONFIG_M2") (pin "5") (pinfunction "5_5") (pintype "passive"))
      (node (ref "U$2") (pin "MS2") (pinfunction "MS2_MS2") (pintype "input"))
    )
    (net (code "83") (name "Net-(NB_STEP_CONFIG_M2-Pad6)") (class "Default")
      (node (ref "NB_STEP_CONFIG_M2") (pin "6") (pinfunction "6_6") (pintype "passive"))
      (node (ref "U$2") (pin "MS3") (pinfunction "MS3_MS3") (pintype "input"))
    )
    (net (code "84") (name "Net-(NB_STEP_CONFIG_M3-Pad4)") (class "Default")
      (node (ref "NB_STEP_CONFIG_M3") (pin "4") (pinfunction "4_4") (pintype "passive"))
      (node (ref "U$3") (pin "MS1") (pinfunction "MS1_MS1") (pintype "input"))
    )
    (net (code "85") (name "Net-(NB_STEP_CONFIG_M3-Pad5)") (class "Default")
      (node (ref "NB_STEP_CONFIG_M3") (pin "5") (pinfunction "5_5") (pintype "passive"))
      (node (ref "U$3") (pin "MS2") (pinfunction "MS2_MS2") (pintype "input"))
    )
    (net (code "86") (name "Net-(NB_STEP_CONFIG_M3-Pad6)") (class "Default")
      (node (ref "NB_STEP_CONFIG_M3") (pin "6") (pinfunction "6_6") (pintype "passive"))
      (node (ref "U$3") (pin "MS3") (pinfunction "MS3_MS3") (pintype "input"))
    )
    (net (code "87") (name "Net-(NB_STEP_CONFIG_M4-Pad4)") (class "Default")
      (node (ref "NB_STEP_CONFIG_M4") (pin "4") (pinfunction "4_4") (pintype "passive"))
      (node (ref "U$4") (pin "MS1") (pinfunction "MS1_MS1") (pintype "input"))
    )
    (net (code "88") (name "Net-(NB_STEP_CONFIG_M4-Pad5)") (class "Default")
      (node (ref "NB_STEP_CONFIG_M4") (pin "5") (pinfunction "5_5") (pintype "passive"))
      (node (ref "U$4") (pin "MS2") (pinfunction "MS2_MS2") (pintype "input"))
    )
    (net (code "89") (name "Net-(NB_STEP_CONFIG_M4-Pad6)") (class "Default")
      (node (ref "NB_STEP_CONFIG_M4") (pin "6") (pinfunction "6_6") (pintype "passive"))
      (node (ref "U$4") (pin "MS3") (pinfunction "MS3_MS3") (pintype "input"))
    )
    (net (code "90") (name "Net-(NB_STEP_CONFIG_M5-Pad4)") (class "Default")
      (node (ref "NB_STEP_CONFIG_M5") (pin "4") (pinfunction "4_4") (pintype "passive"))
      (node (ref "U$5") (pin "MS1") (pinfunction "MS1_MS1") (pintype "input"))
    )
    (net (code "91") (name "Net-(NB_STEP_CONFIG_M5-Pad5)") (class "Default")
      (node (ref "NB_STEP_CONFIG_M5") (pin "5") (pinfunction "5_5") (pintype "passive"))
      (node (ref "U$5") (pin "MS2") (pinfunction "MS2_MS2") (pintype "input"))
    )
    (net (code "92") (name "Net-(NB_STEP_CONFIG_M5-Pad6)") (class "Default")
      (node (ref "NB_STEP_CONFIG_M5") (pin "6") (pinfunction "6_6") (pintype "passive"))
      (node (ref "U$5") (pin "MS3") (pinfunction "MS3_MS3") (pintype "input"))
    )
    (net (code "93") (name "Net-(NB_STEP_CONFIG_M6-Pad4)") (class "Default")
      (node (ref "NB_STEP_CONFIG_M6") (pin "4") (pinfunction "4_4") (pintype "passive"))
      (node (ref "U$6") (pin "MS1") (pinfunction "MS1_MS1") (pintype "input"))
    )
    (net (code "94") (name "Net-(NB_STEP_CONFIG_M6-Pad5)") (class "Default")
      (node (ref "NB_STEP_CONFIG_M6") (pin "5") (pinfunction "5_5") (pintype "passive"))
      (node (ref "U$6") (pin "MS2") (pinfunction "MS2_MS2") (pintype "input"))
    )
    (net (code "95") (name "Net-(NB_STEP_CONFIG_M6-Pad6)") (class "Default")
      (node (ref "NB_STEP_CONFIG_M6") (pin "6") (pinfunction "6_6") (pintype "passive"))
      (node (ref "U$6") (pin "MS3") (pinfunction "MS3_MS3") (pintype "input"))
    )
    (net (code "96") (name "Net-(RESET_SWITCH-P)") (class "Default")
      (node (ref "CONTROL_SWITCHES_INPUTS") (pin "2") (pinfunction "2_2") (pintype "passive"))
      (node (ref "RESET_SWITCH") (pin "3") (pinfunction "P_3") (pintype "passive"))
    )
    (net (code "97") (name "Net-(S2-Pad1)") (class "Default")
      (node (ref "S2") (pin "1") (pinfunction "1_1") (pintype "passive"))
      (node (ref "S2") (pin "2") (pinfunction "2_2") (pintype "passive"))
      (node (ref "SV1") (pin "7") (pinfunction "7_7") (pintype "passive"))
    )
    (net (code "98") (name "Net-(S2-Pad3)") (class "Default")
      (node (ref "S2") (pin "3") (pinfunction "3_3") (pintype "passive"))
      (node (ref "S2") (pin "4") (pinfunction "4_4") (pintype "passive"))
      (node (ref "SV1") (pin "5") (pinfunction "5_5") (pintype "passive"))
    )
    (net (code "99") (name "Net-(S2-Pad5)") (class "Default")
      (node (ref "S2") (pin "5") (pinfunction "5_5") (pintype "passive"))
      (node (ref "S2") (pin "6") (pinfunction "6_6") (pintype "passive"))
      (node (ref "SV1") (pin "3") (pinfunction "3_3") (pintype "passive"))
    )
    (net (code "100") (name "Net-(S2-Pad7)") (class "Default")
      (node (ref "S2") (pin "7") (pinfunction "7_7") (pintype "passive"))
      (node (ref "S2") (pin "8") (pinfunction "8_8") (pintype "passive"))
      (node (ref "SV1") (pin "1") (pinfunction "1_1") (pintype "passive"))
    )
    (net (code "101") (name "Net-(U$1-SLEEP)") (class "Default")
      (node (ref "U$1") (pin "RST") (pinfunction "RST_RST") (pintype "input"))
      (node (ref "U$1") (pin "SLP") (pinfunction "SLEEP_SLP") (pintype "input"))
    )
    (net (code "102") (name "Net-(U$2-SLEEP)") (class "Default")
      (node (ref "U$2") (pin "RST") (pinfunction "RST_RST") (pintype "input"))
      (node (ref "U$2") (pin "SLP") (pinfunction "SLEEP_SLP") (pintype "input"))
    )
    (net (code "103") (name "Net-(U$3-SLEEP)") (class "Default")
      (node (ref "U$3") (pin "RST") (pinfunction "RST_RST") (pintype "input"))
      (node (ref "U$3") (pin "SLP") (pinfunction "SLEEP_SLP") (pintype "input"))
    )
    (net (code "104") (name "Net-(U$4-SLEEP)") (class "Default")
      (node (ref "U$4") (pin "RST") (pinfunction "RST_RST") (pintype "input"))
      (node (ref "U$4") (pin "SLP") (pinfunction "SLEEP_SLP") (pintype "input"))
    )
    (net (code "105") (name "Net-(U$5-SLEEP)") (class "Default")
      (node (ref "U$5") (pin "RST") (pinfunction "RST_RST") (pintype "input"))
      (node (ref "U$5") (pin "SLP") (pinfunction "SLEEP_SLP") (pintype "input"))
    )
    (net (code "106") (name "Net-(U$6-SLEEP)") (class "Default")
      (node (ref "U$6") (pin "RST") (pinfunction "RST_RST") (pintype "input"))
      (node (ref "U$6") (pin "SLP") (pinfunction "SLEEP_SLP") (pintype "input"))
    )
    (net (code "107") (name "unconnected-(ARDUINO_DUE1-5V-Pad5V0)") (class "Default")
      (node (ref "ARDUINO_DUE1") (pin "5V0") (pinfunction "5V_5V0") (pintype "bidirectional"))
    )
    (net (code "108") (name "unconnected-(ARDUINO_DUE1-AN5-PadA5)") (class "Default")
      (node (ref "ARDUINO_DUE1") (pin "A5") (pinfunction "AN5_A5") (pintype "bidirectional"))
    )
    (net (code "109") (name "unconnected-(ARDUINO_DUE1-AN7-PadA7)") (class "Default")
      (node (ref "ARDUINO_DUE1") (pin "A7") (pinfunction "AN7_A7") (pintype "bidirectional"))
    )
    (net (code "110") (name "unconnected-(ARDUINO_DUE1-AN8-PadA8)") (class "Default")
      (node (ref "ARDUINO_DUE1") (pin "A8") (pinfunction "AN8_A8") (pintype "bidirectional"))
    )
    (net (code "111") (name "unconnected-(ARDUINO_DUE1-AN9-PadA9)") (class "Default")
      (node (ref "ARDUINO_DUE1") (pin "A9") (pinfunction "AN9_A9") (pintype "bidirectional"))
    )
    (net (code "112") (name "unconnected-(ARDUINO_DUE1-AN10-PadA10)") (class "Default")
      (node (ref "ARDUINO_DUE1") (pin "A10") (pinfunction "AN10_A10") (pintype "bidirectional"))
    )
    (net (code "113") (name "unconnected-(ARDUINO_DUE1-AN11-PadA11)") (class "Default")
      (node (ref "ARDUINO_DUE1") (pin "A11") (pinfunction "AN11_A11") (pintype "bidirectional"))
    )
    (net (code "114") (name "unconnected-(ARDUINO_DUE1-GND-PadGND_4)") (class "Default")
      (node (ref "ARDUINO_DUE1") (pin "GND_4") (pinfunction "GND_GND_4") (pintype "bidirectional"))
    )
    (net (code "115") (name "unconnected-(ARDUINO_DUE1-NC-PadNC_2)") (class "Default")
      (node (ref "ARDUINO_DUE1") (pin "NC_2") (pinfunction "NC_NC_2") (pintype "no_connect"))
    )
    (net (code "116") (name "unconnected-(ARDUINO_DUE1-Pad10)") (class "Default")
      (node (ref "ARDUINO_DUE1") (pin "10") (pinfunction "10_10") (pintype "bidirectional"))
    )
    (net (code "117") (name "unconnected-(ARDUINO_DUE1-Pad47)") (class "Default")
      (node (ref "ARDUINO_DUE1") (pin "47") (pinfunction "47_47") (pintype "bidirectional"))
    )
    (net (code "118") (name "unconnected-(ARDUINO_DUE1-Pad48)") (class "Default")
      (node (ref "ARDUINO_DUE1") (pin "48") (pinfunction "48_48") (pintype "bidirectional"))
    )
    (net (code "119") (name "unconnected-(ARDUINO_DUE1-Pad49)") (class "Default")
      (node (ref "ARDUINO_DUE1") (pin "49") (pinfunction "49_49") (pintype "bidirectional"))
    )
    (net (code "120") (name "unconnected-(ARDUINO_DUE1-Pad50)") (class "Default")
      (node (ref "ARDUINO_DUE1") (pin "50") (pinfunction "50_50") (pintype "bidirectional"))
    )
    (net (code "121") (name "unconnected-(ARDUINO_DUE1-Pad51)") (class "Default")
      (node (ref "ARDUINO_DUE1") (pin "51") (pinfunction "51_51") (pintype "bidirectional"))
    )
    (net (code "122") (name "unconnected-(ARDUINO_DUE1-Pad52)") (class "Default")
      (node (ref "ARDUINO_DUE1") (pin "52") (pinfunction "52_52") (pintype "bidirectional"))
    )
    (net (code "123") (name "unconnected-(ARDUINO_DUE1-Pad53)") (class "Default")
      (node (ref "ARDUINO_DUE1") (pin "53") (pinfunction "53_53") (pintype "bidirectional"))
    )
    (net (code "124") (name "unconnected-(ARDUINO_DUE1-PadAREF)") (class "Default")
      (node (ref "ARDUINO_DUE1") (pin "AREF") (pinfunction "AREF_AREF") (pintype "bidirectional"))
    )
    (net (code "125") (name "unconnected-(ARDUINO_DUE1-PadCANRX)") (class "Default")
      (node (ref "ARDUINO_DUE1") (pin "CANRX") (pinfunction "CANRX_CANRX") (pintype "bidirectional"))
    )
    (net (code "126") (name "unconnected-(ARDUINO_DUE1-PadCANTX)") (class "Default")
      (node (ref "ARDUINO_DUE1") (pin "CANTX") (pinfunction "CANTX_CANTX") (pintype "bidirectional"))
    )
    (net (code "127") (name "unconnected-(ARDUINO_DUE1-PadDAC0)") (class "Default")
      (node (ref "ARDUINO_DUE1") (pin "DAC0") (pinfunction "DAC0_DAC0") (pintype "bidirectional"))
    )
    (net (code "128") (name "unconnected-(ARDUINO_DUE1-PadDAC1)") (class "Default")
      (node (ref "ARDUINO_DUE1") (pin "DAC1") (pinfunction "DAC1_DAC1") (pintype "bidirectional"))
    )
    (net (code "129") (name "unconnected-(ARDUINO_DUE1-PadIOREF)") (class "Default")
      (node (ref "ARDUINO_DUE1") (pin "IOREF") (pinfunction "IOREF_IOREF") (pintype "bidirectional"))
    )
    (net (code "130") (name "unconnected-(ARDUINO_DUE1-PadSCL1)") (class "Default")
      (node (ref "ARDUINO_DUE1") (pin "SCL1") (pinfunction "SCL1_SCL1") (pintype "bidirectional"))
    )
    (net (code "131") (name "unconnected-(ARDUINO_DUE1-PadSDA1)") (class "Default")
      (node (ref "ARDUINO_DUE1") (pin "SDA1") (pinfunction "SDA1_SDA1") (pintype "bidirectional"))
    )
    (net (code "132") (name "unconnected-(ARDUINO_DUE1-PadVIN)") (class "Default")
      (node (ref "ARDUINO_DUE1") (pin "VIN") (pinfunction "VIN_VIN") (pintype "bidirectional"))
    )
    (net (code "133") (name "unconnected-(ARDUINO_DUE1-RX0<0-Pad0)") (class "Default")
      (node (ref "ARDUINO_DUE1") (pin "0") (pinfunction "RX0<0_0") (pintype "bidirectional"))
    )
    (net (code "134") (name "unconnected-(ARDUINO_DUE1-SCL_21-Pad21)") (class "Default")
      (node (ref "ARDUINO_DUE1") (pin "21") (pinfunction "SCL_21_21") (pintype "bidirectional"))
    )
    (net (code "135") (name "unconnected-(ARDUINO_DUE1-SDA_20-Pad20)") (class "Default")
      (node (ref "ARDUINO_DUE1") (pin "20") (pinfunction "SDA_20_20") (pintype "bidirectional"))
    )
    (net (code "136") (name "unconnected-(ARDUINO_DUE1-TX0>1-Pad1)") (class "Default")
      (node (ref "ARDUINO_DUE1") (pin "1") (pinfunction "TX0>1_1") (pintype "bidirectional"))
    )
    (net (code "137") (name "unconnected-(MOTOR_POWER-Pad2)") (class "Default")
      (node (ref "MOTOR_POWER") (pin "2") (pinfunction "2_2") (pintype "passive"))
    )
  )
)
